# PCB_LED_MonitorFluorecente.net
KiCad netlist of a schematic drawn in Altium Designer
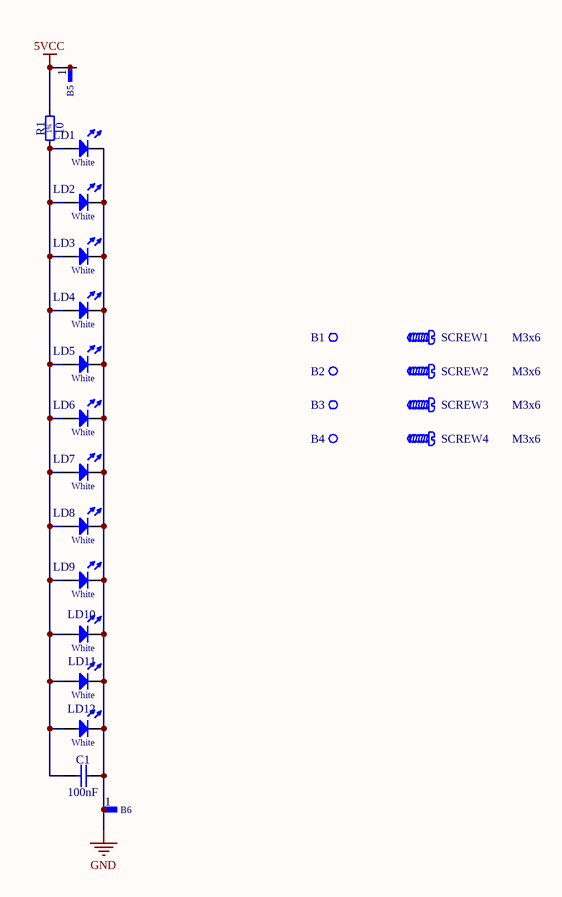
[diagram p0: PCB LED_MonitorFluorecente.SchDoc]

(export (version "E")
  (design (tool "Eeschema 10.0.6"))
  (components
    (comp (ref "B1")
      (value "Plated Hole")
      (footprint "MTG320_1050")
      (description "Single Terminal Socket")
      (fields (field (name "PART NUMBER") "PLATED_HOLE3.2_PAD10.5") (field (name "AUTHOR") "CERN DEM JMW"))
      (libsource (lib "Eletro-mechanical") (part "Single Terminal Socket"))
    )
    (comp (ref "B2")
      (value "Plated Hole")
      (footprint "MTG320_1050")
      (description "Single Terminal Socket")
      (fields (field (name "PART NUMBER") "PLATED_HOLE3.2_PAD10.5") (field (name "AUTHOR") "CERN DEM JMW"))
      (libsource (lib "Eletro-mechanical") (part "Single Terminal Socket"))
    )
    (comp (ref "B3")
      (value "Plated Hole")
      (footprint "MTG320_1050")
      (description "Single Terminal Socket")
      (fields (field (name "PART NUMBER") "PLATED_HOLE3.2_PAD10.5") (field (name "AUTHOR") "CERN DEM JMW"))
      (libsource (lib "Eletro-mechanical") (part "Single Terminal Socket"))
    )
    (comp (ref "B4")
      (value "Plated Hole")
      (footprint "MTG320_1050")
      (description "Single Terminal Socket")
      (fields (field (name "PART NUMBER") "PLATED_HOLE3.2_PAD10.5") (field (name "AUTHOR") "CERN DEM JMW"))
      (libsource (lib "Eletro-mechanical") (part "Single Terminal Socket"))
    )
    (comp (ref "B5")
      (value "SMD Pad")
      (footprint "R400X300")
      (description "Single SMD Pad")
      (fields (field (name "PART NUMBER") "SMD_PAD_4X3MM") (field (name "AUTHOR") "CERN DEM JLC"))
      (libsource (lib "") (part "Single SMD Pad_1"))
    )
    (comp (ref "B6")
      (value "SMD Pad")
      (footprint "R400X300")
      (description "Single SMD Pad")
      (fields (field (name "PART NUMBER") "SMD_PAD_4X3MM") (field (name "AUTHOR") "CERN DEM JLC"))
      (libsource (lib "Eletro-mechanical") (part "Single SMD Pad"))
    )
    (comp (ref "C1")
      (value "100nF")
      (footprint "CAPC2012X135N")
      (description "Non-polarised capacitor")
      (fields
        (field (name "PART NUMBER") "CC0805_100NF_50V_10%_X7R")
        (field (name "VOLTAGE") "50V")
        (field (name "AUTHOR") "CERN DEM JLC")
      )
      (libsource (lib "Capacitors") (part "Capacitor - non polarized"))
    )
    (comp (ref "LD1")
      (value "White")
      (footprint "LED_OSRAM_GW_JTLPS1.EM")
      (description "LED White 1C 2A")
      (fields
        (field (name "MANUFACTURER") "OSRAM")
        (field (name "MANUFACTURER PART NUMBER") "GW JTLPS1.EM-KKKM-XX55-1-150-R33")
        (field (name "AUTHOR") "LNLS DIG LOS")
      )
      (libsource (lib "ICs And Semiconductors_LNLS") (part "LED White 1C 2A"))
    )
    (comp (ref "LD2")
      (value "White")
      (footprint "LED_OSRAM_GW_JTLPS1.EM")
      (description "LED White 1C 2A")
      (fields
        (field (name "MANUFACTURER") "OSRAM")
        (field (name "MANUFACTURER PART NUMBER") "GW JTLPS1.EM-KKKM-XX55-1-150-R33")
        (field (name "AUTHOR") "LNLS DIG LOS")
      )
      (libsource (lib "ICs And Semiconductors_LNLS") (part "LED White 1C 2A"))
    )
    (comp (ref "LD3")
      (value "White")
      (footprint "LED_OSRAM_GW_JTLPS1.EM")
      (description "LED White 1C 2A")
      (fields
        (field (name "MANUFACTURER") "OSRAM")
        (field (name "MANUFACTURER PART NUMBER") "GW JTLPS1.EM-KKKM-XX55-1-150-R33")
        (field (name "AUTHOR") "LNLS DIG LOS")
      )
      (libsource (lib "ICs And Semiconductors_LNLS") (part "LED White 1C 2A"))
    )
    (comp (ref "LD4")
      (value "White")
      (footprint "LED_OSRAM_GW_JTLPS1.EM")
      (description "LED White 1C 2A")
      (fields
        (field (name "MANUFACTURER") "OSRAM")
        (field (name "MANUFACTURER PART NUMBER") "GW JTLPS1.EM-KKKM-XX55-1-150-R33")
        (field (name "AUTHOR") "LNLS DIG LOS")
      )
      (libsource (lib "ICs And Semiconductors_LNLS") (part "LED White 1C 2A"))
    )
    (comp (ref "LD5")
      (value "White")
      (footprint "LED_OSRAM_GW_JTLPS1.EM")
      (description "LED White 1C 2A")
      (fields
        (field (name "MANUFACTURER") "OSRAM")
        (field (name "MANUFACTURER PART NUMBER") "GW JTLPS1.EM-KKKM-XX55-1-150-R33")
        (field (name "AUTHOR") "LNLS DIG LOS")
      )
      (libsource (lib "ICs And Semiconductors_LNLS") (part "LED White 1C 2A"))
    )
    (comp (ref "LD6")
      (value "White")
      (footprint "LED_OSRAM_GW_JTLPS1.EM")
      (description "LED White 1C 2A")
      (fields
        (field (name "MANUFACTURER") "OSRAM")
        (field (name "MANUFACTURER PART NUMBER") "GW JTLPS1.EM-KKKM-XX55-1-150-R33")
        (field (name "AUTHOR") "LNLS DIG LOS")
      )
      (libsource (lib "ICs And Semiconductors_LNLS") (part "LED White 1C 2A"))
    )
    (comp (ref "LD7")
      (value "White")
      (footprint "LED_OSRAM_GW_JTLPS1.EM")
      (description "LED White 1C 2A")
      (fields
        (field (name "MANUFACTURER") "OSRAM")
        (field (name "MANUFACTURER PART NUMBER") "GW JTLPS1.EM-KKKM-XX55-1-150-R33")
        (field (name "AUTHOR") "LNLS DIG LOS")
      )
      (libsource (lib "ICs And Semiconductors_LNLS") (part "LED White 1C 2A"))
    )
    (comp (ref "LD8")
      (value "White")
      (footprint "LED_OSRAM_GW_JTLPS1.EM")
      (description "LED White 1C 2A")
      (fields
        (field (name "MANUFACTURER") "OSRAM")
        (field (name "MANUFACTURER PART NUMBER") "GW JTLPS1.EM-KKKM-XX55-1-150-R33")
        (field (name "AUTHOR") "LNLS DIG LOS")
      )
      (libsource (lib "ICs And Semiconductors_LNLS") (part "LED White 1C 2A"))
    )
    (comp (ref "LD9")
      (value "White")
      (footprint "LED_OSRAM_GW_JTLPS1.EM")
      (description "LED White 1C 2A")
      (fields
        (field (name "MANUFACTURER") "OSRAM")
        (field (name "MANUFACTURER PART NUMBER") "GW JTLPS1.EM-KKKM-XX55-1-150-R33")
        (field (name "AUTHOR") "LNLS DIG LOS")
      )
      (libsource (lib "ICs And Semiconductors_LNLS") (part "LED White 1C 2A"))
    )
    (comp (ref "LD10")
      (value "White")
      (footprint "LED_OSRAM_GW_JTLPS1.EM")
      (description "LED White 1C 2A")
      (fields
        (field (name "MANUFACTURER") "OSRAM")
        (field (name "MANUFACTURER PART NUMBER") "GW JTLPS1.EM-KKKM-XX55-1-150-R33")
        (field (name "AUTHOR") "LNLS DIG LOS")
      )
      (libsource (lib "ICs And Semiconductors_LNLS") (part "LED White 1C 2A"))
    )
    (comp (ref "LD11")
      (value "White")
      (footprint "LED_OSRAM_GW_JTLPS1.EM")
      (description "LED White 1C 2A")
      (fields
        (field (name "MANUFACTURER") "OSRAM")
        (field (name "MANUFACTURER PART NUMBER") "GW JTLPS1.EM-KKKM-XX55-1-150-R33")
        (field (name "AUTHOR") "LNLS DIG LOS")
      )
      (libsource (lib "ICs And Semiconductors_LNLS") (part "LED White 1C 2A"))
    )
    (comp (ref "LD12")
      (value "White")
      (footprint "LED_OSRAM_GW_JTLPS1.EM")
      (description "LED White 1C 2A")
      (fields
        (field (name "MANUFACTURER") "OSRAM")
        (field (name "MANUFACTURER PART NUMBER") "GW JTLPS1.EM-KKKM-XX55-1-150-R33")
        (field (name "AUTHOR") "LNLS DIG LOS")
      )
      (libsource (lib "ICs And Semiconductors_LNLS") (part "LED White 1C 2A"))
    )
    (comp (ref "R1")
      (value "10")
      (footprint "RESC3216X65N")
      (description "Resistor - 1%")
      (fields
        (field (name "PART NUMBER") "R1206_10R_1%_0.25W_200PPM")
        (field (name "POWER") "0.25W")
        (field (name "AUTHOR") "CERN DEM JLC")
      )
      (libsource (lib "Resistors") (part "Resistor - 1%"))
    )
    (comp (ref "SCREW1")
      (value "M3x6")
      (footprint "BOSSARD_BN1061-1401173_v")
      (description "Slotted Pan Head Screw")
      (fields
        (field (name "PART NUMBER") "BOSSARD_BN1061-1401173_v")
        (field (name "MANUFACTURER") "BOSSARD")
        (field (name "AUTHOR") "CERN DEM JMW")
      )
      (libsource (lib "Eletro-mechanical") (part "Screw - Slotted Pan Head"))
    )
    (comp (ref "SCREW2")
      (value "M3x6")
      (footprint "BOSSARD_BN1061-1401173_v")
      (description "Slotted Pan Head Screw")
      (fields
        (field (name "PART NUMBER") "BOSSARD_BN1061-1401173_v")
        (field (name "MANUFACTURER") "BOSSARD")
        (field (name "AUTHOR") "CERN DEM JMW")
      )
      (libsource (lib "Eletro-mechanical") (part "Screw - Slotted Pan Head"))
    )
    (comp (ref "SCREW3")
      (value "M3x6")
      (footprint "BOSSARD_BN1061-1401173_v")
      (description "Slotted Pan Head Screw")
      (fields
        (field (name "PART NUMBER") "BOSSARD_BN1061-1401173_v")
        (field (name "MANUFACTURER") "BOSSARD")
        (field (name "AUTHOR") "CERN DEM JMW")
      )
      (libsource (lib "Eletro-mechanical") (part "Screw - Slotted Pan Head"))
    )
    (comp (ref "SCREW4")
      (value "M3x6")
      (footprint "BOSSARD_BN1061-1401173_v")
      (description "Slotted Pan Head Screw")
      (fields
        (field (name "PART NUMBER") "BOSSARD_BN1061-1401173_v")
        (field (name "MANUFACTURER") "BOSSARD")
        (field (name "AUTHOR") "CERN DEM JMW")
      )
      (libsource (lib "Eletro-mechanical") (part "Screw - Slotted Pan Head"))
    )
  )
  (nets
    (net (code "1") (name "5VCC") (class "Default")
      (node (ref "B5") (pin "1") (pinfunction "1_1") (pintype "bidirectional"))
      (node (ref "R1") (pin "2") (pinfunction "2_2") (pintype "passive"))
    )
    (net (code "2") (name "GND") (class "Default")
      (node (ref "B6") (pin "1") (pinfunction "1_1") (pintype "bidirectional"))
      (node (ref "C1") (pin "2") (pinfunction "2_2") (pintype "passive"))
      (node (ref "LD1") (pin "1") (pinfunction "C_1") (pintype "passive"))
      (node (ref "LD10") (pin "1") (pinfunction "C_1") (pintype "passive"))
      (node (ref "LD11") (pin "1") (pinfunction "C_1") (pintype "passive"))
      (node (ref "LD12") (pin "1") (pinfunction "C_1") (pintype "passive"))
      (node (ref "LD2") (pin "1") (pinfunction "C_1") (pintype "passive"))
      (node (ref "LD3") (pin "1") (pinfunction "C_1") (pintype "passive"))
      (node (ref "LD4") (pin "1") (pinfunction "C_1") (pintype "passive"))
      (node (ref "LD5") (pin "1") (pinfunction "C_1") (pintype "passive"))
      (node (ref "LD6") (pin "1") (pinfunction "C_1") (pintype "passive"))
      (node (ref "LD7") (pin "1") (pinfunction "C_1") (pintype "passive"))
      (node (ref "LD8") (pin "1") (pinfunction "C_1") (pintype "passive"))
      (node (ref "LD9") (pin "1") (pinfunction "C_1") (pintype "passive"))
    )
    (net (code "3") (name "Net-(LD1-A)") (class "Default")
      (node (ref "C1") (pin "1") (pinfunction "1_1") (pintype "passive"))
      (node (ref "LD1") (pin "2") (pinfunction "A_2") (pintype "passive"))
      (node (ref "LD10") (pin "2") (pinfunction "A_2") (pintype "passive"))
      (node (ref "LD11") (pin "2") (pinfunction "A_2") (pintype "passive"))
      (node (ref "LD12") (pin "2") (pinfunction "A_2") (pintype "passive"))
      (node (ref "LD2") (pin "2") (pinfunction "A_2") (pintype "passive"))
      (node (ref "LD3") (pin "2") (pinfunction "A_2") (pintype "passive"))
      (node (ref "LD4") (pin "2") (pinfunction "A_2") (pintype "passive"))
      (node (ref "LD5") (pin "2") (pinfunction "A_2") (pintype "passive"))
      (node (ref "LD6") (pin "2") (pinfunction "A_2") (pintype "passive"))
      (node (ref "LD7") (pin "2") (pinfunction "A_2") (pintype "passive"))
      (node (ref "LD8") (pin "2") (pinfunction "A_2") (pintype "passive"))
      (node (ref "LD9") (pin "2") (pinfunction "A_2") (pintype "passive"))
      (node (ref "R1") (pin "1") (pinfunction "1_1") (pintype "passive"))
    )
    (net (code "4") (name "unconnected-(B1-Pad1)") (class "Default")
      (node (ref "B1") (pin "1") (pinfunction "1_1") (pintype "bidirectional"))
    )
    (net (code "5") (name "unconnected-(B2-Pad1)") (class "Default")
      (node (ref "B2") (pin "1") (pinfunction "1_1") (pintype "bidirectional"))
    )
    (net (code "6") (name "unconnected-(B3-Pad1)") (class "Default")
      (node (ref "B3") (pin "1") (pinfunction "1_1") (pintype "bidirectional"))
    )
    (net (code "7") (name "unconnected-(B4-Pad1)") (class "Default")
      (node (ref "B4") (pin "1") (pinfunction "1_1") (pintype "bidirectional"))
    )
  )
)
